# Sheet1.net
KiCad netlist of a schematic drawn in Altium Designer
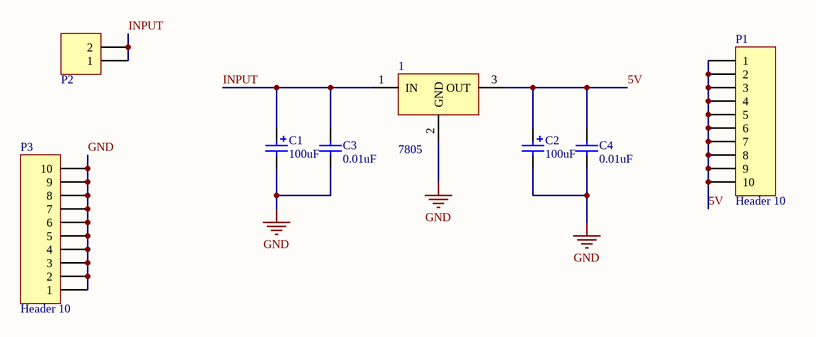
[diagram p0: Sheet1.SchDoc]

(export (version "E")
  (design (tool "Eeschema 10.0.6"))
  (components
    (comp (ref "1") (value "7805") (footprint "TO-220") (libsource (lib "Voltage电压基准") (part "7805")))
    (comp (ref "C1")
      (value "100uF")
      (footprint "RB2")
      (fields (field (name "Comment") "Cap2"))
      (libsource (lib "MY") (part "Cap2"))
    )
    (comp (ref "C2")
      (value "100uF")
      (footprint "RB2")
      (fields (field (name "Comment") "Cap2"))
      (libsource (lib "MY") (part "Cap2"))
    )
    (comp (ref "C3")
      (value "0.01uF")
      (footprint "RAD0.1")
      (fields (field (name "Comment") "Cap1"))
      (libsource (lib "MY") (part "Cap1"))
    )
    (comp (ref "C4")
      (value "0.01uF")
      (footprint "RAD0.1")
      (fields (field (name "Comment") "Cap1"))
      (libsource (lib "MY") (part "Cap1"))
    )
    (comp (ref "P1")
      (value "Header 10")
      (footprint "SIP-10")
      (description "Header, 10-Pin")
      (fields (field (name "PUBLISHER") "Altium Limited"))
      (libsource (lib "") (part "Header 10_1"))
    )
    (comp (ref "P2")
      (value "Header 2")
      (footprint "HDR2X1_A")
      (description "接插件")
      (fields (field (name "PUBLISHER") "Altium Limited"))
      (libsource (lib "Fszhang") (part "Header 2"))
    )
    (comp (ref "P3")
      (value "Header 10")
      (footprint "SIP-10")
      (description "Header, 10-Pin")
      (fields (field (name "PUBLISHER") "Altium Limited"))
      (libsource (lib "Fszhang") (part "Header 10"))
    )
  )
  (nets
    (net (code "1") (name "/5V") (class "Default")
      (node (ref "1") (pin "3") (pinfunction "OUT_3") (pintype "passive"))
      (node (ref "C2") (pin "1") (pinfunction "1_1") (pintype "passive"))
      (node (ref "C4") (pin "2") (pinfunction "2_2") (pintype "passive"))
      (node (ref "P1") (pin "1") (pinfunction "1_1") (pintype "passive"))
      (node (ref "P1") (pin "10") (pinfunction "10_10") (pintype "passive"))
      (node (ref "P1") (pin "2") (pinfunction "2_2") (pintype "passive"))
      (node (ref "P1") (pin "3") (pinfunction "3_3") (pintype "passive"))
      (node (ref "P1") (pin "4") (pinfunction "4_4") (pintype "passive"))
      (node (ref "P1") (pin "5") (pinfunction "5_5") (pintype "passive"))
      (node (ref "P1") (pin "6") (pinfunction "6_6") (pintype "passive"))
      (node (ref "P1") (pin "7") (pinfunction "7_7") (pintype "passive"))
      (node (ref "P1") (pin "8") (pinfunction "8_8") (pintype "passive"))
      (node (ref "P1") (pin "9") (pinfunction "9_9") (pintype "passive"))
    )
    (net (code "2") (name "/INPUT") (class "Default")
      (node (ref "1") (pin "1") (pinfunction "IN_1") (pintype "passive"))
      (node (ref "C1") (pin "1") (pinfunction "1_1") (pintype "passive"))
      (node (ref "C3") (pin "2") (pinfunction "2_2") (pintype "passive"))
      (node (ref "P2") (pin "1") (pinfunction "1_1") (pintype "passive"))
      (node (ref "P2") (pin "2") (pinfunction "2_2") (pintype "passive"))
    )
    (net (code "3") (name "GND") (class "Default")
      (node (ref "1") (pin "2") (pinfunction "GND_2") (pintype "passive"))
      (node (ref "C1") (pin "2") (pinfunction "2_2") (pintype "passive"))
      (node (ref "C2") (pin "2") (pinfunction "2_2") (pintype "passive"))
      (node (ref "C3") (pin "1") (pinfunction "1_1") (pintype "passive"))
      (node (ref "C4") (pin "1") (pinfunction "1_1") (pintype "passive"))
      (node (ref "P3") (pin "1") (pinfunction "1_1") (pintype "passive"))
      (node (ref "P3") (pin "10") (pinfunction "10_10") (pintype "passive"))
      (node (ref "P3") (pin "2") (pinfunction "2_2") (pintype "passive"))
      (node (ref "P3") (pin "3") (pinfunction "3_3") (pintype "passive"))
      (node (ref "P3") (pin "4") (pinfunction "4_4") (pintype "passive"))
      (node (ref "P3") (pin "5") (pinfunction "5_5") (pintype "passive"))
      (node (ref "P3") (pin "6") (pinfunction "6_6") (pintype "passive"))
      (node (ref "P3") (pin "7") (pinfunction "7_7") (pintype "passive"))
      (node (ref "P3") (pin "8") (pinfunction "8_8") (pintype "passive"))
      (node (ref "P3") (pin "9") (pinfunction "9_9") (pintype "passive"))
    )
  )
)
